# Flash.net
KiCad netlist of a schematic drawn in Altium Designer
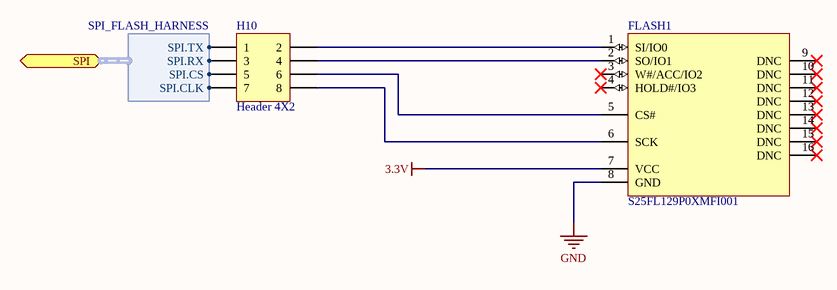
[diagram p0: Flash.SchDoc]

(export (version "E")
  (design (tool "Eeschema 10.0.6"))
  (components
    (comp (ref "FLASH1")
      (value "S25FL129P0XMFI001")
      (footprint "SOIC-16-FLASH")
      (libsource (lib "Vector Library") (part "S25FL129P0XMFI001"))
    )
    (comp (ref "H10")
      (value "Header 4X2")
      (footprint "HDR2X4")
      (description "Header, 4-Pin, Dual row")
      (fields (field (name "PUBLISHER") "Altium Limited"))
      (libsource (lib "Miscellaneous Connectors") (part "Header 4X2"))
    )
  )
  (nets
    (net (code "2") (name "/SPI.CLK") (class "Default")
      (node (ref "H10") (pin "7") (pinfunction "7_7") (pintype "passive"))
    )
    (net (code "3") (name "/SPI.CS") (class "Default")
      (node (ref "H10") (pin "5") (pinfunction "5_5") (pintype "passive"))
    )
    (net (code "4") (name "/SPI.RX") (class "Default")
      (node (ref "H10") (pin "3") (pinfunction "3_3") (pintype "passive"))
    )
    (net (code "5") (name "/SPI.TX") (class "Default")
      (node (ref "H10") (pin "1") (pinfunction "1_1") (pintype "passive"))
    )
    (net (code "7") (name "3.3V") (class "Default")
      (node (ref "FLASH1") (pin "7") (pinfunction "VCC_7") (pintype "passive"))
    )
    (net (code "8") (name "GND") (class "Default")
      (node (ref "FLASH1") (pin "8") (pinfunction "GND_8") (pintype "passive"))
    )
    (net (code "9") (name "Net-(FLASH1-CS#)") (class "Default")
      (node (ref "FLASH1") (pin "5") (pinfunction "CS#_5") (pintype "passive"))
      (node (ref "H10") (pin "6") (pinfunction "6_6") (pintype "passive"))
    )
    (net (code "10") (name "Net-(FLASH1-SCK)") (class "Default")
      (node (ref "FLASH1") (pin "6") (pinfunction "SCK_6") (pintype "passive"))
      (node (ref "H10") (pin "8") (pinfunction "8_8") (pintype "passive"))
    )
    (net (code "11") (name "Net-(FLASH1-SI{slash}IO0)") (class "Default")
      (node (ref "FLASH1") (pin "1") (pinfunction "SI/IO0_1") (pintype "bidirectional"))
      (node (ref "H10") (pin "2") (pinfunction "2_2") (pintype "passive"))
    )
    (net (code "12") (name "Net-(FLASH1-SO{slash}IO1)") (class "Default")
      (node (ref "FLASH1") (pin "2") (pinfunction "SO/IO1_2") (pintype "bidirectional"))
      (node (ref "H10") (pin "4") (pinfunction "4_4") (pintype "passive"))
    )
    (net (code "13") (name "unconnected-(FLASH1-DNC-Pad9)") (class "Default")
      (node (ref "FLASH1") (pin "9") (pinfunction "DNC_9") (pintype "passive+no_connect"))
    )
    (net (code "14") (name "unconnected-(FLASH1-DNC-Pad10)") (class "Default")
      (node (ref "FLASH1") (pin "10") (pinfunction "DNC_10") (pintype "passive+no_connect"))
    )
    (net (code "15") (name "unconnected-(FLASH1-DNC-Pad11)") (class "Default")
      (node (ref "FLASH1") (pin "11") (pinfunction "DNC_11") (pintype "passive+no_connect"))
    )
    (net (code "16") (name "unconnected-(FLASH1-DNC-Pad12)") (class "Default")
      (node (ref "FLASH1") (pin "12") (pinfunction "DNC_12") (pintype "passive+no_connect"))
    )
    (net (code "17") (name "unconnected-(FLASH1-DNC-Pad13)") (class "Default")
      (node (ref "FLASH1") (pin "13") (pinfunction "DNC_13") (pintype "passive+no_connect"))
    )
    (net (code "18") (name "unconnected-(FLASH1-DNC-Pad14)") (class "Default")
      (node (ref "FLASH1") (pin "14") (pinfunction "DNC_14") (pintype "passive+no_connect"))
    )
    (net (code "19") (name "unconnected-(FLASH1-DNC-Pad15)") (class "Default")
      (node (ref "FLASH1") (pin "15") (pinfunction "DNC_15") (pintype "passive+no_connect"))
    )
    (net (code "20") (name "unconnected-(FLASH1-DNC-Pad16)") (class "Default")
      (node (ref "FLASH1") (pin "16") (pinfunction "DNC_16") (pintype "passive+no_connect"))
    )
    (net (code "21") (name "unconnected-(FLASH1-HOLD#{slash}IO3-Pad4)") (class "Default")
      (node (ref "FLASH1") (pin "4") (pinfunction "HOLD#/IO3_4") (pintype "bidirectional+no_connect"))
    )
    (net (code "22") (name "unconnected-(FLASH1-W#{slash}ACC{slash}IO2-Pad3)") (class "Default")
      (node (ref "FLASH1") (pin "3") (pinfunction "W#/ACC/IO2_3") (pintype "bidirectional+no_connect"))
    )
  )
)
